# Loop_Filter_AD8065.net
KiCad netlist of a schematic drawn in Altium Designer
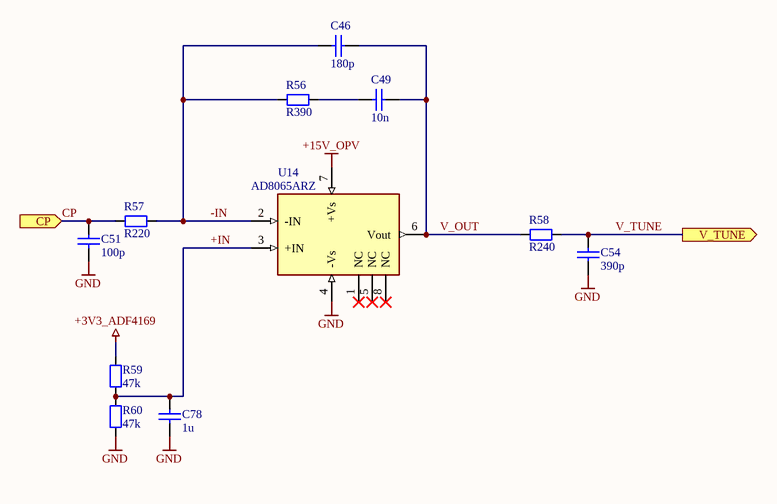
[diagram p0: Loop_Filter_AD8065.SchDoc]

(export (version "E")
  (design (tool "Eeschema 10.0.6"))
  (components
    (comp (ref "C46")
      (value "180p")
      (footprint "C_0603_1608Metric_IPC_N")
      (description "Generic MLCC with 0603 Footprint")
      (libsource (lib "database_library") (part "Capacitor_unpol"))
    )
    (comp (ref "C49")
      (value "10n")
      (footprint "C_0603_1608Metric_IPC_N")
      (description "Generic MLCC with 0603 Footprint")
      (libsource (lib "database_library") (part "Capacitor_unpol"))
    )
    (comp (ref "C51")
      (value "100p")
      (footprint "C_0603_1608Metric_IPC_N")
      (description "Generic MLCC with 0603 Footprint")
      (libsource (lib "database_library") (part "Capacitor_unpol"))
    )
    (comp (ref "C54")
      (value "390p")
      (footprint "C_0603_1608Metric_IPC_N")
      (description "Generic MLCC with 0603 Footprint")
      (libsource (lib "database_library") (part "Capacitor_unpol"))
    )
    (comp (ref "C78")
      (value "1u")
      (footprint "C_0603_1608Metric_IPC_N")
      (description "Generic MLCC with 0603 Footprint")
      (libsource (lib "database_library") (part "Capacitor_unpol"))
    )
    (comp (ref "R56")
      (value "R390")
      (footprint "R_0603_1608Metric_IPC_N")
      (description "Generic Chip Resistor with 0603 Footprint")
      (libsource (lib "database_library") (part "Resistor"))
    )
    (comp (ref "R57")
      (value "R220")
      (footprint "R_0603_1608Metric_IPC_N")
      (description "Generic Chip Resistor with 0603 Footprint")
      (libsource (lib "database_library") (part "Resistor"))
    )
    (comp (ref "R58")
      (value "R240")
      (footprint "R_0603_1608Metric_IPC_N")
      (description "Generic Chip Resistor with 0603 Footprint")
      (libsource (lib "database_library") (part "Resistor"))
    )
    (comp (ref "R59")
      (value "47k")
      (footprint "R_0603_1608Metric_IPC_N")
      (description "Generic Chip Resistor with 0603 Footprint")
      (libsource (lib "database_library") (part "Resistor"))
    )
    (comp (ref "R60")
      (value "47k")
      (footprint "R_0603_1608Metric_IPC_N")
      (description "Generic Chip Resistor with 0603 Footprint")
      (libsource (lib "database_library") (part "Resistor"))
    )
    (comp (ref "U14")
      (value "AD8065ARZ")
      (footprint "SOIC-8_3.9x4.9mm_P1.27mm_IPC_N")
      (fields (field (name "MANUFACTURER") "Analog Devices"))
      (libsource (lib "database_library") (part "AD8065"))
    )
  )
  (nets
    (net (code "1") (name "+3V3_ADF4169") (class "Default")
      (node (ref "R59") (pin "2") (pinfunction "2_2") (pintype "passive"))
    )
    (net (code "2") (name "+15V_OPV") (class "Default")
      (node (ref "U14") (pin "7") (pinfunction "+Vs_7") (pintype "input"))
    )
    (net (code "3") (name "/+IN") (class "Default")
      (node (ref "C78") (pin "2") (pinfunction "2_2") (pintype "passive"))
      (node (ref "R59") (pin "1") (pinfunction "1_1") (pintype "passive"))
      (node (ref "R60") (pin "2") (pinfunction "2_2") (pintype "passive"))
      (node (ref "U14") (pin "3") (pinfunction "+IN_3") (pintype "input"))
    )
    (net (code "4") (name "/-IN") (class "Default")
      (node (ref "C46") (pin "2") (pinfunction "2_2") (pintype "passive"))
      (node (ref "R56") (pin "2") (pinfunction "2_2") (pintype "passive"))
      (node (ref "R57") (pin "1") (pinfunction "1_1") (pintype "passive"))
      (node (ref "U14") (pin "2") (pinfunction "-IN_2") (pintype "input"))
    )
    (net (code "5") (name "/CP") (class "Default")
      (node (ref "C51") (pin "1") (pinfunction "1_1") (pintype "passive"))
      (node (ref "R57") (pin "2") (pinfunction "2_2") (pintype "passive"))
    )
    (net (code "6") (name "/V_OUT") (class "Default")
      (node (ref "C46") (pin "1") (pinfunction "1_1") (pintype "passive"))
      (node (ref "C49") (pin "1") (pinfunction "1_1") (pintype "passive"))
      (node (ref "R58") (pin "2") (pinfunction "2_2") (pintype "passive"))
      (node (ref "U14") (pin "6") (pinfunction "Vout_6") (pintype "output"))
    )
    (net (code "7") (name "/V_TUNE") (class "Default")
      (node (ref "C54") (pin "2") (pinfunction "2_2") (pintype "passive"))
      (node (ref "R58") (pin "1") (pinfunction "1_1") (pintype "passive"))
    )
    (net (code "8") (name "GND") (class "Default")
      (node (ref "C51") (pin "2") (pinfunction "2_2") (pintype "passive"))
      (node (ref "C54") (pin "1") (pinfunction "1_1") (pintype "passive"))
      (node (ref "C78") (pin "1") (pinfunction "1_1") (pintype "passive"))
      (node (ref "R60") (pin "1") (pinfunction "1_1") (pintype "passive"))
      (node (ref "U14") (pin "4") (pinfunction "-Vs_4") (pintype "input"))
    )
    (net (code "9") (name "Net-(C49-Pad2)") (class "Default")
      (node (ref "C49") (pin "2") (pinfunction "2_2") (pintype "passive"))
      (node (ref "R56") (pin "1") (pinfunction "1_1") (pintype "passive"))
    )
    (net (code "10") (name "unconnected-(U14-NC-Pad1)") (class "Default")
      (node (ref "U14") (pin "1") (pinfunction "NC_1") (pintype "passive+no_connect"))
    )
    (net (code "11") (name "unconnected-(U14-NC-Pad5)") (class "Default")
      (node (ref "U14") (pin "5") (pinfunction "NC_5") (pintype "passive+no_connect"))
    )
    (net (code "12") (name "unconnected-(U14-NC-Pad8)") (class "Default")
      (node (ref "U14") (pin "8") (pinfunction "NC_8") (pintype "passive+no_connect"))
    )
  )
)
